# SThuMb32.net
KiCad netlist of a schematic drawn in Altium Designer
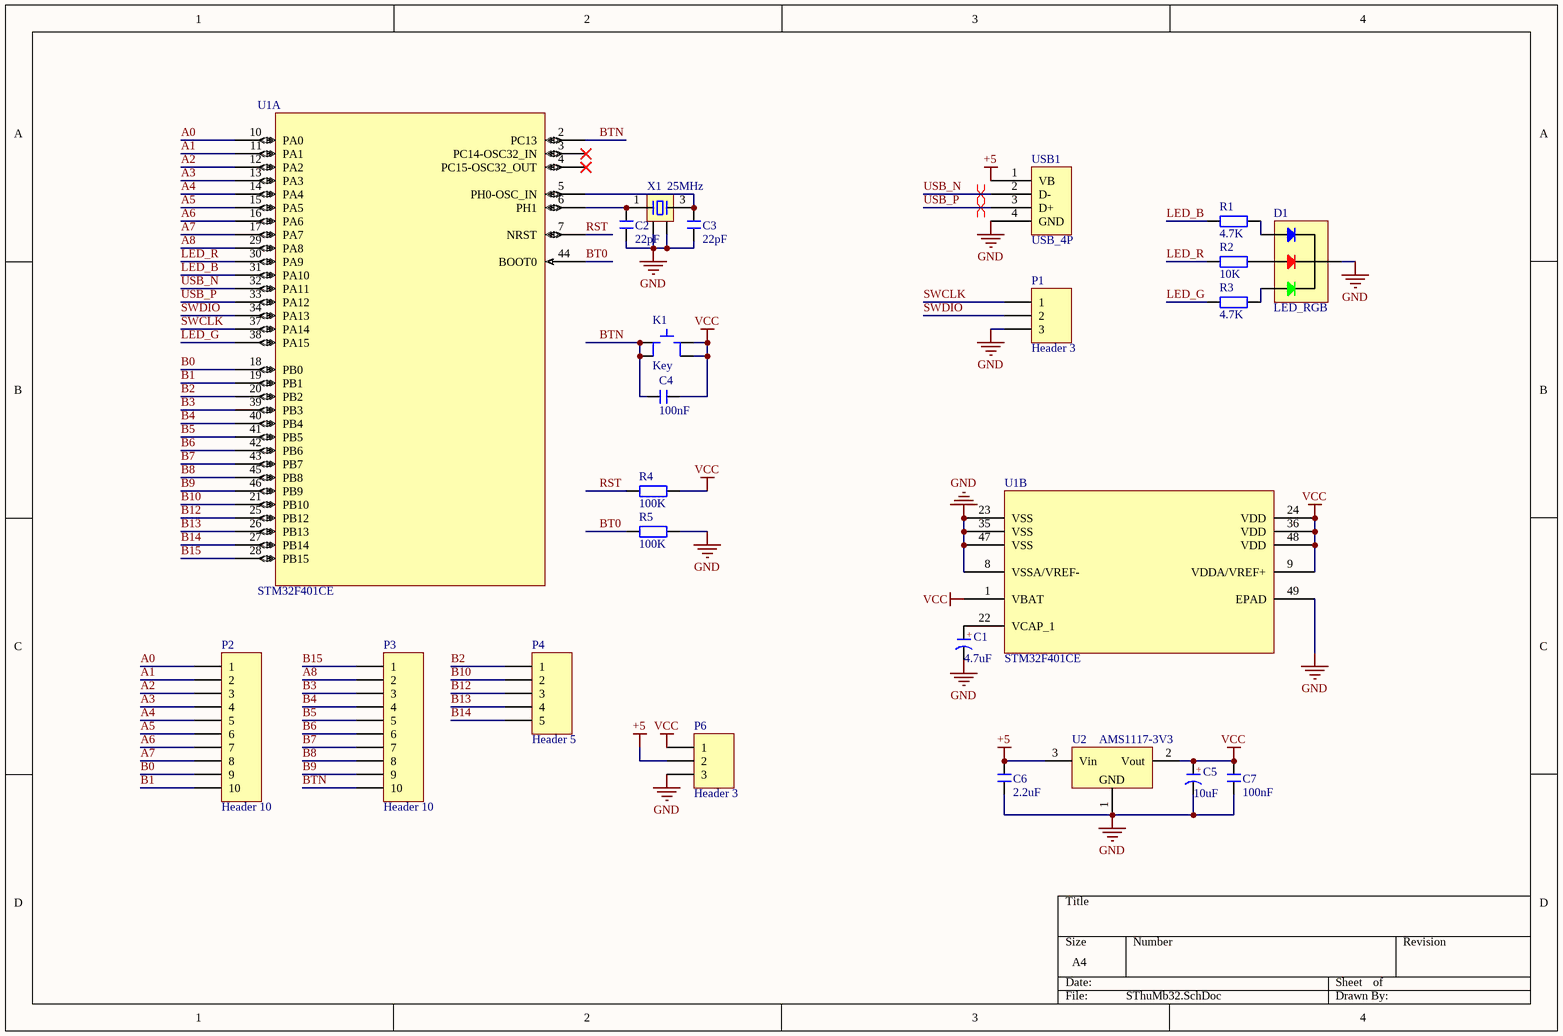
[diagram p0: SThuMb32.SchDoc]

(export (version "E")
  (design (tool "Eeschema 10.0.6"))
  (components
    (comp (ref "C1")
      (value "4.7uF")
      (footprint "CD A(3216)")
      (description "贴片钽电容")
      (libsource (lib "淘宝买的") (part "CT"))
    )
    (comp (ref "C2")
      (value "22pF")
      (footprint "C 0603_L")
      (description "贴片电容")
      (libsource (lib "淘宝买的") (part "C"))
    )
    (comp (ref "C3")
      (value "22pF")
      (footprint "C 0603_L")
      (description "贴片电容")
      (libsource (lib "淘宝买的") (part "C"))
    )
    (comp (ref "C4")
      (value "100nF")
      (footprint "C 0603_L")
      (description "贴片电容")
      (libsource (lib "淘宝买的") (part "C"))
    )
    (comp (ref "C5")
      (value "10uF")
      (footprint "CD A(3216)")
      (description "贴片钽电容")
      (libsource (lib "淘宝买的") (part "CT"))
    )
    (comp (ref "C6")
      (value "2.2uF")
      (footprint "C 0603_L")
      (description "贴片电容")
      (libsource (lib "淘宝买的") (part "C"))
    )
    (comp (ref "C7")
      (value "100nF")
      (footprint "C 0603_L")
      (description "贴片电容")
      (libsource (lib "淘宝买的") (part "C"))
    )
    (comp (ref "D1")
      (value "LED_RGB")
      (footprint "LED_RGB_0606")
      (description "RGB共阴LED")
      (libsource (lib "Schlib") (part "LED_RGB"))
    )
    (comp (ref "K1") (value "Key") (footprint "Key_4x4_4P") (libsource (lib "Schlib") (part "Key_4P")))
    (comp (ref "P1")
      (value "Header 3")
      (footprint "HDR1X3")
      (description "Header, 3-Pin")
      (fields (field (name "PUBLISHER") "Altium Limited"))
      (libsource (lib "Miscellaneous Connectors") (part "Header 3"))
    )
    (comp (ref "P2")
      (value "Header 10")
      (footprint "HDR1X10")
      (description "Header, 10-Pin")
      (fields (field (name "PUBLISHER") "Altium Limited"))
      (libsource (lib "Miscellaneous Connectors") (part "Header 10"))
    )
    (comp (ref "P3")
      (value "Header 10")
      (footprint "HDR1X10")
      (description "Header, 10-Pin")
      (fields (field (name "PUBLISHER") "Altium Limited"))
      (libsource (lib "Miscellaneous Connectors") (part "Header 10"))
    )
    (comp (ref "P4")
      (value "Header 5")
      (footprint "HDR1X5")
      (description "Header, 5-Pin")
      (fields (field (name "PUBLISHER") "Altium Limited"))
      (libsource (lib "Miscellaneous Connectors") (part "Header 5"))
    )
    (comp (ref "P6")
      (value "Header 3")
      (footprint "HDR1X3")
      (description "Header, 3-Pin")
      (fields (field (name "PUBLISHER") "Altium Limited"))
      (libsource (lib "Miscellaneous Connectors") (part "Header 3"))
    )
    (comp (ref "R1")
      (value "4.7K")
      (footprint "R 0603_L")
      (description "贴片电阻")
      (fields (field (name "版权归属") "来自淘宝 ID：黄晶宝石"))
      (libsource (lib "淘宝买的") (part "R"))
    )
    (comp (ref "R2")
      (value "10K")
      (footprint "R 0603_L")
      (description "贴片电阻")
      (fields (field (name "版权归属") "来自淘宝 ID：黄晶宝石"))
      (libsource (lib "淘宝买的") (part "R"))
    )
    (comp (ref "R3")
      (value "4.7K")
      (footprint "R 0603_L")
      (description "贴片电阻")
      (fields (field (name "版权归属") "来自淘宝 ID：黄晶宝石"))
      (libsource (lib "淘宝买的") (part "R"))
    )
    (comp (ref "R4")
      (value "100K")
      (footprint "R 0603_L")
      (description "贴片电阻")
      (fields (field (name "版权归属") "来自淘宝 ID：黄晶宝石"))
      (libsource (lib "淘宝买的") (part "R"))
    )
    (comp (ref "R5")
      (value "100K")
      (footprint "R 0603_L")
      (description "贴片电阻")
      (fields (field (name "版权归属") "来自淘宝 ID：黄晶宝石"))
      (libsource (lib "淘宝买的") (part "R"))
    )
    (comp (ref "U1")
      (value "STM32F401CE")
      (footprint "UFQFPN-48_7X7_L")
      (description "带DSP和FPU的高性能基本型系列ARM Cortex-M4 MCU，具有512 KB Flash、84 MHz CPU和ART加速器")
      (fields
        (field (name "MANUFACTURER_PART_NUMBER") "stm32f4xxc1")
        (field (name "COPYRIGHT") "Copyright (C) 2016 Accelerated Designs. All rights reserved")
      )
      (libsource (lib "Schlib") (part "STM32F401CE"))
    )
    (comp (ref "U2")
      (value "AMS1117-3V3")
      (footprint "SOT223_L")
      (description "三端稳压芯片")
      (libsource (lib "淘宝买的") (part "AMS1117"))
    )
    (comp (ref "USB1") (value "USB_4P") (footprint "USB_A_Male") (libsource (lib "Schlib") (part "USB_4P")))
    (comp (ref "X1")
      (value "25MHz")
      (footprint "OSC 3225-4P")
      (description "4脚无源晶振")
      (fields (field (name "版权归属") "封装库来自淘宝卖家 ID：黄晶宝石"))
      (libsource (lib "淘宝买的") (part "XTAL-4P"))
    )
  )
  (nets
    (net (code "1") (name "+5") (class "Default")
      (node (ref "C6") (pin "2") (pinfunction "2_2") (pintype "passive"))
      (node (ref "P6") (pin "2") (pinfunction "2_2") (pintype "passive"))
      (node (ref "U2") (pin "3") (pinfunction "Vin_3") (pintype "passive"))
      (node (ref "USB1") (pin "1") (pinfunction "VB_1") (pintype "passive"))
    )
    (net (code "2") (name "/A0") (class "Default")
      (node (ref "P2") (pin "1") (pinfunction "1_1") (pintype "passive"))
      (node (ref "U1") (pin "10") (pinfunction "PA0_10") (pintype "bidirectional"))
    )
    (net (code "3") (name "/A1") (class "Default")
      (node (ref "P2") (pin "2") (pinfunction "2_2") (pintype "passive"))
      (node (ref "U1") (pin "11") (pinfunction "PA1_11") (pintype "bidirectional"))
    )
    (net (code "4") (name "/A2") (class "Default")
      (node (ref "P2") (pin "3") (pinfunction "3_3") (pintype "passive"))
      (node (ref "U1") (pin "12") (pinfunction "PA2_12") (pintype "bidirectional"))
    )
    (net (code "5") (name "/A3") (class "Default")
      (node (ref "P2") (pin "4") (pinfunction "4_4") (pintype "passive"))
      (node (ref "U1") (pin "13") (pinfunction "PA3_13") (pintype "bidirectional"))
    )
    (net (code "6") (name "/A4") (class "Default")
      (node (ref "P2") (pin "5") (pinfunction "5_5") (pintype "passive"))
      (node (ref "U1") (pin "14") (pinfunction "PA4_14") (pintype "bidirectional"))
    )
    (net (code "7") (name "/A5") (class "Default")
      (node (ref "P2") (pin "6") (pinfunction "6_6") (pintype "passive"))
      (node (ref "U1") (pin "15") (pinfunction "PA5_15") (pintype "bidirectional"))
    )
    (net (code "8") (name "/A6") (class "Default")
      (node (ref "P2") (pin "7") (pinfunction "7_7") (pintype "passive"))
      (node (ref "U1") (pin "16") (pinfunction "PA6_16") (pintype "bidirectional"))
    )
    (net (code "9") (name "/A7") (class "Default")
      (node (ref "P2") (pin "8") (pinfunction "8_8") (pintype "passive"))
      (node (ref "U1") (pin "17") (pinfunction "PA7_17") (pintype "bidirectional"))
    )
    (net (code "10") (name "/A8") (class "Default")
      (node (ref "P3") (pin "2") (pinfunction "2_2") (pintype "passive"))
      (node (ref "U1") (pin "29") (pinfunction "PA8_29") (pintype "bidirectional"))
    )
    (net (code "11") (name "/B0") (class "Default")
      (node (ref "P2") (pin "9") (pinfunction "9_9") (pintype "passive"))
      (node (ref "U1") (pin "18") (pinfunction "PB0_18") (pintype "bidirectional"))
    )
    (net (code "12") (name "/B1") (class "Default")
      (node (ref "P2") (pin "10") (pinfunction "10_10") (pintype "passive"))
      (node (ref "U1") (pin "19") (pinfunction "PB1_19") (pintype "bidirectional"))
    )
    (net (code "13") (name "/B2") (class "Default")
      (node (ref "P4") (pin "1") (pinfunction "1_1") (pintype "passive"))
      (node (ref "U1") (pin "20") (pinfunction "PB2_20") (pintype "bidirectional"))
    )
    (net (code "14") (name "/B3") (class "Default")
      (node (ref "P3") (pin "3") (pinfunction "3_3") (pintype "passive"))
      (node (ref "U1") (pin "39") (pinfunction "PB3_39") (pintype "bidirectional"))
    )
    (net (code "15") (name "/B4") (class "Default")
      (node (ref "P3") (pin "4") (pinfunction "4_4") (pintype "passive"))
      (node (ref "U1") (pin "40") (pinfunction "PB4_40") (pintype "bidirectional"))
    )
    (net (code "16") (name "/B5") (class "Default")
      (node (ref "P3") (pin "5") (pinfunction "5_5") (pintype "passive"))
      (node (ref "U1") (pin "41") (pinfunction "PB5_41") (pintype "bidirectional"))
    )
    (net (code "17") (name "/B6") (class "Default")
      (node (ref "P3") (pin "6") (pinfunction "6_6") (pintype "passive"))
      (node (ref "U1") (pin "42") (pinfunction "PB6_42") (pintype "bidirectional"))
    )
    (net (code "18") (name "/B7") (class "Default")
      (node (ref "P3") (pin "7") (pinfunction "7_7") (pintype "passive"))
      (node (ref "U1") (pin "43") (pinfunction "PB7_43") (pintype "bidirectional"))
    )
    (net (code "19") (name "/B8") (class "Default")
      (node (ref "P3") (pin "8") (pinfunction "8_8") (pintype "passive"))
      (node (ref "U1") (pin "45") (pinfunction "PB8_45") (pintype "bidirectional"))
    )
    (net (code "20") (name "/B9") (class "Default")
      (node (ref "P3") (pin "9") (pinfunction "9_9") (pintype "passive"))
      (node (ref "U1") (pin "46") (pinfunction "PB9_46") (pintype "bidirectional"))
    )
    (net (code "21") (name "/B10") (class "Default")
      (node (ref "P4") (pin "2") (pinfunction "2_2") (pintype "passive"))
      (node (ref "U1") (pin "21") (pinfunction "PB10_21") (pintype "bidirectional"))
    )
    (net (code "22") (name "/B12") (class "Default")
      (node (ref "P4") (pin "3") (pinfunction "3_3") (pintype "passive"))
      (node (ref "U1") (pin "25") (pinfunction "PB12_25") (pintype "bidirectional"))
    )
    (net (code "23") (name "/B13") (class "Default")
      (node (ref "P4") (pin "4") (pinfunction "4_4") (pintype "passive"))
      (node (ref "U1") (pin "26") (pinfunction "PB13_26") (pintype "bidirectional"))
    )
    (net (code "24") (name "/B14") (class "Default")
      (node (ref "P4") (pin "5") (pinfunction "5_5") (pintype "passive"))
      (node (ref "U1") (pin "27") (pinfunction "PB14_27") (pintype "bidirectional"))
    )
    (net (code "25") (name "/B15") (class "Default")
      (node (ref "P3") (pin "1") (pinfunction "1_1") (pintype "passive"))
      (node (ref "U1") (pin "28") (pinfunction "PB15_28") (pintype "bidirectional"))
    )
    (net (code "26") (name "/BT0") (class "Default")
      (node (ref "R5") (pin "1") (pinfunction "1_1") (pintype "passive"))
      (node (ref "U1") (pin "44") (pinfunction "BOOT0_44") (pintype "input"))
    )
    (net (code "27") (name "/BTN") (class "Default")
      (node (ref "C4") (pin "1") (pinfunction "1_1") (pintype "passive"))
      (node (ref "K1") (pin "1") (pinfunction "1_1") (pintype "passive"))
      (node (ref "K1") (pin "3") (pinfunction "3_3") (pintype "passive"))
      (node (ref "P3") (pin "10") (pinfunction "10_10") (pintype "passive"))
      (node (ref "U1") (pin "2") (pinfunction "PC13_2") (pintype "bidirectional"))
    )
    (net (code "28") (name "/LED_B") (class "Default")
      (node (ref "R1") (pin "1") (pinfunction "1_1") (pintype "passive"))
      (node (ref "U1") (pin "31") (pinfunction "PA10_31") (pintype "bidirectional"))
    )
    (net (code "29") (name "/LED_G") (class "Default")
      (node (ref "R3") (pin "1") (pinfunction "1_1") (pintype "passive"))
      (node (ref "U1") (pin "38") (pinfunction "PA15_38") (pintype "bidirectional"))
    )
    (net (code "30") (name "/LED_R") (class "Default")
      (node (ref "R2") (pin "1") (pinfunction "1_1") (pintype "passive"))
      (node (ref "U1") (pin "30") (pinfunction "PA9_30") (pintype "bidirectional"))
    )
    (net (code "31") (name "/RST") (class "Default")
      (node (ref "R4") (pin "1") (pinfunction "1_1") (pintype "passive"))
      (node (ref "U1") (pin "7") (pinfunction "NRST_7") (pintype "bidirectional"))
    )
    (net (code "32") (name "/SWCLK") (class "Default")
      (node (ref "P1") (pin "1") (pinfunction "1_1") (pintype "passive"))
      (node (ref "U1") (pin "37") (pinfunction "PA14_37") (pintype "bidirectional"))
    )
    (net (code "33") (name "/SWDIO") (class "Default")
      (node (ref "P1") (pin "2") (pinfunction "2_2") (pintype "passive"))
      (node (ref "U1") (pin "34") (pinfunction "PA13_34") (pintype "bidirectional"))
    )
    (net (code "34") (name "/USB_N") (class "Default")
      (node (ref "U1") (pin "32") (pinfunction "PA11_32") (pintype "bidirectional"))
      (node (ref "USB1") (pin "2") (pinfunction "D-_2") (pintype "passive"))
    )
    (net (code "35") (name "/USB_P") (class "Default")
      (node (ref "U1") (pin "33") (pinfunction "PA12_33") (pintype "bidirectional"))
      (node (ref "USB1") (pin "3") (pinfunction "D+_3") (pintype "passive"))
    )
    (net (code "36") (name "GND") (class "Default")
      (node (ref "C1") (pin "2") (pinfunction "K_2") (pintype "passive"))
      (node (ref "C2") (pin "1") (pinfunction "1_1") (pintype "passive"))
      (node (ref "C3") (pin "1") (pinfunction "1_1") (pintype "passive"))
      (node (ref "C5") (pin "2") (pinfunction "K_2") (pintype "passive"))
      (node (ref "C6") (pin "1") (pinfunction "1_1") (pintype "passive"))
      (node (ref "C7") (pin "1") (pinfunction "1_1") (pintype "passive"))
      (node (ref "D1") (pin "1") (pinfunction "COM_1") (pintype "passive"))
      (node (ref "P1") (pin "3") (pinfunction "3_3") (pintype "passive"))
      (node (ref "P6") (pin "3") (pinfunction "3_3") (pintype "passive"))
      (node (ref "R5") (pin "2") (pinfunction "2_2") (pintype "passive"))
      (node (ref "U1") (pin "23") (pinfunction "VSS_23") (pintype "power_in"))
      (node (ref "U1") (pin "35") (pinfunction "VSS_35") (pintype "power_in"))
      (node (ref "U1") (pin "47") (pinfunction "VSS_47") (pintype "power_in"))
      (node (ref "U1") (pin "49") (pinfunction "EPAD_49") (pintype "passive"))
      (node (ref "U1") (pin "8") (pinfunction "VSSA/VREF-_8") (pintype "power_in"))
      (node (ref "U2") (pin "1") (pinfunction "GND_1") (pintype "passive"))
      (node (ref "USB1") (pin "4") (pinfunction "GND_4") (pintype "passive"))
      (node (ref "X1") (pin "2") (pinfunction "2_2") (pintype "passive"))
      (node (ref "X1") (pin "4") (pinfunction "4_4") (pintype "passive"))
    )
    (net (code "37") (name "Net-(C1-A)") (class "Default")
      (node (ref "C1") (pin "1") (pinfunction "A_1") (pintype "passive"))
      (node (ref "U1") (pin "22") (pinfunction "VCAP_1_22") (pintype "power_in"))
    )
    (net (code "38") (name "Net-(D1-B)") (class "Default")
      (node (ref "D1") (pin "4") (pinfunction "B_4") (pintype "passive"))
      (node (ref "R1") (pin "2") (pinfunction "2_2") (pintype "passive"))
    )
    (net (code "39") (name "Net-(D1-G)") (class "Default")
      (node (ref "D1") (pin "3") (pinfunction "G_3") (pintype "passive"))
      (node (ref "R3") (pin "2") (pinfunction "2_2") (pintype "passive"))
    )
    (net (code "40") (name "Net-(D1-R)") (class "Default")
      (node (ref "D1") (pin "2") (pinfunction "R_2") (pintype "passive"))
      (node (ref "R2") (pin "2") (pinfunction "2_2") (pintype "passive"))
    )
    (net (code "41") (name "Net-(U1A-PH0-OSC_IN)") (class "Default")
      (node (ref "C3") (pin "2") (pinfunction "2_2") (pintype "passive"))
      (node (ref "U1") (pin "5") (pinfunction "PH0-OSC_IN_5") (pintype "bidirectional"))
      (node (ref "X1") (pin "3") (pinfunction "3_3") (pintype "passive"))
    )
    (net (code "42") (name "Net-(U1A-PH1)") (class "Default")
      (node (ref "C2") (pin "2") (pinfunction "2_2") (pintype "passive"))
      (node (ref "U1") (pin "6") (pinfunction "PH1_6") (pintype "bidirectional"))
      (node (ref "X1") (pin "1") (pinfunction "1_1") (pintype "passive"))
    )
    (net (code "43") (name "VCC") (class "Default")
      (node (ref "C4") (pin "2") (pinfunction "2_2") (pintype "passive"))
      (node (ref "C5") (pin "1") (pinfunction "A_1") (pintype "passive"))
      (node (ref "C7") (pin "2") (pinfunction "2_2") (pintype "passive"))
      (node (ref "K1") (pin "2") (pinfunction "2_2") (pintype "passive"))
      (node (ref "K1") (pin "4") (pinfunction "4_4") (pintype "passive"))
      (node (ref "P6") (pin "1") (pinfunction "1_1") (pintype "passive"))
      (node (ref "R4") (pin "2") (pinfunction "2_2") (pintype "passive"))
      (node (ref "U1") (pin "1") (pinfunction "VBAT_1") (pintype "power_in"))
      (node (ref "U1") (pin "24") (pinfunction "VDD_24") (pintype "power_in"))
      (node (ref "U1") (pin "36") (pinfunction "VDD_36") (pintype "power_in"))
      (node (ref "U1") (pin "48") (pinfunction "VDD_48") (pintype "power_in"))
      (node (ref "U1") (pin "9") (pinfunction "VDDA/VREF+_9") (pintype "power_in"))
      (node (ref "U2") (pin "2") (pinfunction "Vout_2") (pintype "passive"))
    )
    (net (code "44") (name "unconnected-(U1A-PC14-OSC32_IN-Pad3)") (class "Default")
      (node (ref "U1") (pin "3") (pinfunction "PC14-OSC32_IN_3") (pintype "bidirectional+no_connect"))
    )
    (net (code "45") (name "unconnected-(U1A-PC15-OSC32_OUT-Pad4)") (class "Default")
      (node (ref "U1") (pin "4") (pinfunction "PC15-OSC32_OUT_4") (pintype "bidirectional+no_connect"))
    )
  )
)
